# In_Amp.net
KiCad netlist of a schematic drawn in Altium Designer
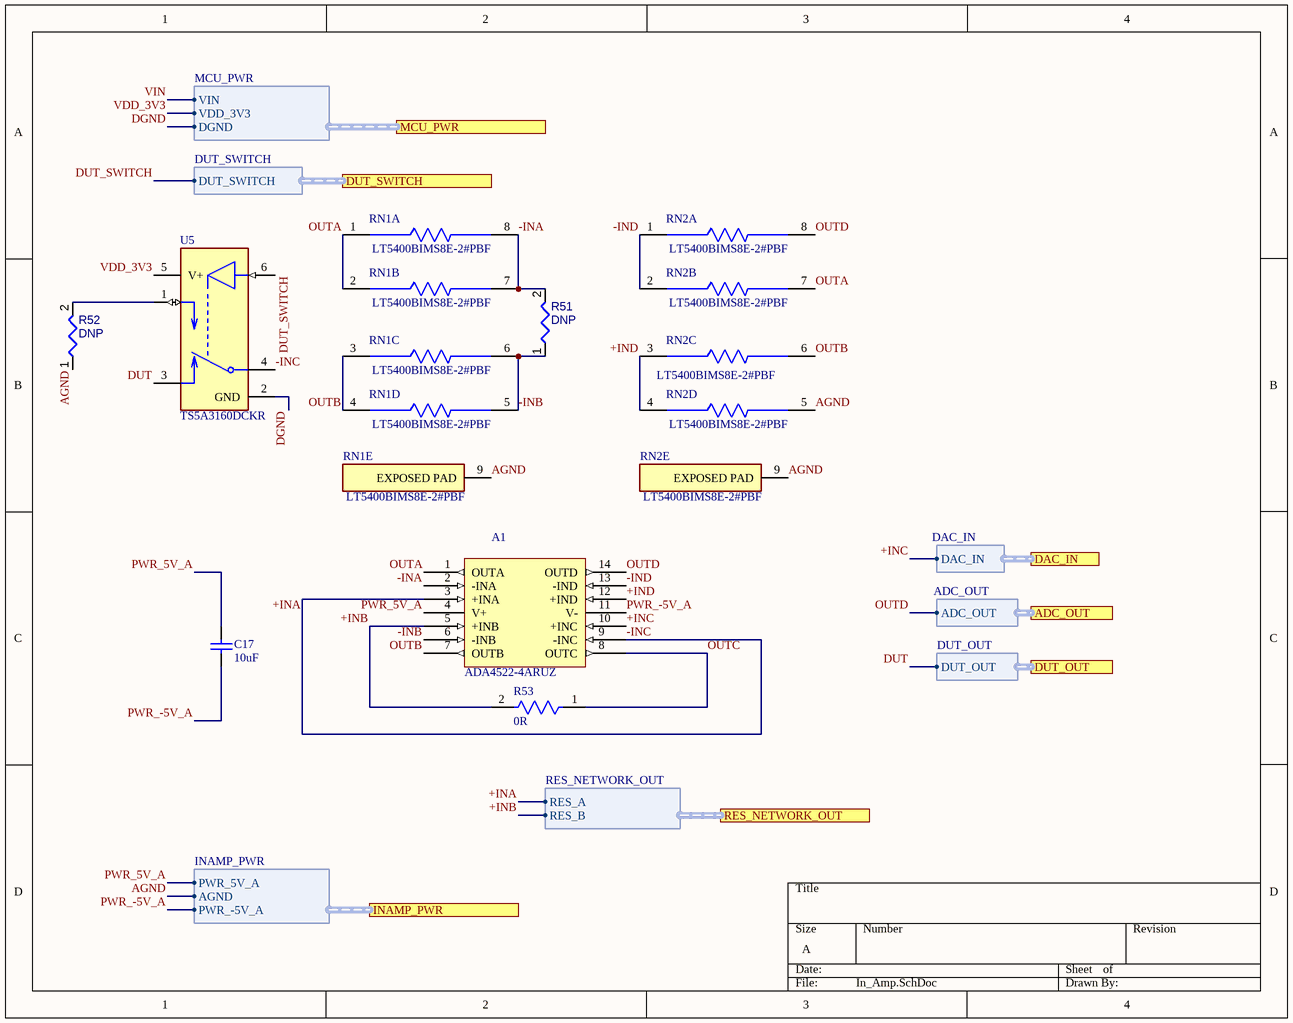
[diagram p0: In_Amp.SchDoc]

(export (version "E")
  (design (tool "Eeschema 10.0.6"))
  (components
    (comp (ref "A1")
      (value "ADA4522-4ARUZ")
      (footprint "TSSOP14")
      (libsource (lib "SchematicLibLovro") (part "AD4522-4ARUZ"))
    )
    (comp (ref "C17")
      (value "10uF")
      (footprint "CAPC2013X135X45ML10T25")
      (fields (field (name "PART NUMBER") "GRM21BR61E106KA73L") (field (name "MANUFACTURER") "Murata"))
      (libsource (lib "Altium Content Vault") (part "CAP"))
    )
    (comp (ref "R51")
      (value "DNP")
      (footprint "RESC1608X55X25ML10T15")
      (description "do not place")
      (libsource (lib "Lovro's workspace") (part "RES-2"))
    )
    (comp (ref "R52")
      (value "DNP")
      (footprint "RESC1608X55X25ML10T15")
      (description "do not place")
      (libsource (lib "Lovro's workspace") (part "RES-2"))
    )
    (comp (ref "R53")
      (value "0R")
      (footprint "FP-CR0603-MFG")
      (description "Thick Film Chip Resistors 0603 0Ω 0.1W 5%")
      (fields (field (name "TOLERANCE") "1%"))
      (libsource (lib "Altium Content Vault") (part "1029c3af85768c4190bb7ad29bc67b5"))
    )
    (comp (ref "RN1")
      (value "LT5400BIMS8E-2#PBF")
      (footprint "FP-MS8E-8-05-08-1662-MFG")
      (description "RES ARRAY 4 RES 1K OHM 8TSSOP")
      (fields
        (field (name "OCTOPART") "https://octopart.com/lt5400ahms8e-4%23pbf-analog+devices-88940367")
        (field (name "MANUFACTURER") "Analog Devices")
      )
      (libsource (lib "Altium Content Vault") (part "2a3fcee17dfe07ed204b7d70d1dfd57"))
    )
    (comp (ref "RN2")
      (value "LT5400BIMS8E-2#PBF")
      (footprint "FP-MS8E-8-05-08-1662-MFG")
      (description "RES ARRAY 4 RES 1K OHM 8TSSOP")
      (fields
        (field (name "OCTOPART") "https://octopart.com/lt5400ahms8e-4%23pbf-analog+devices-88940367")
        (field (name "MANUFACTURER") "Analog Devices")
      )
      (libsource (lib "Altium Content Vault") (part "2a3fcee17dfe07ed204b7d70d1dfd57"))
    )
    (comp (ref "U5")
      (value "TS5A3160DCKR")
      (footprint "FP-DCK0006A-MFG")
      (description "IC SWITCH SPDT SC70-6")
      (fields
        (field (name "OCTOPART") "https://octopart.com/ts5a3160dckr-texas+instruments-665387")
        (field (name "MANUFACTURER") "Texas Instruments")
      )
      (libsource (lib "Altium Content Vault") (part "dd16568d2eba44a85523cc31585f9e4"))
    )
  )
  (nets
    (net (code "7") (name "/+INA") (class "Default")
      (node (ref "A1") (pin "3") (pinfunction "+INA_3") (pintype "input"))
      (node (ref "A1") (pin "9") (pinfunction "-INC_9") (pintype "input"))
      (node (ref "U5") (pin "4") (pinfunction "COM_4") (pintype "passive"))
    )
    (net (code "8") (name "/+INB") (class "Default")
      (node (ref "A1") (pin "5") (pinfunction "+INB_5") (pintype "input"))
      (node (ref "R53") (pin "2") (pinfunction "2_2") (pintype "passive"))
    )
    (net (code "9") (name "/+INC") (class "Default")
      (node (ref "A1") (pin "10") (pinfunction "+INC_10") (pintype "input"))
    )
    (net (code "10") (name "/+IND") (class "Default")
      (node (ref "A1") (pin "12") (pinfunction "+IND_12") (pintype "input"))
      (node (ref "RN2") (pin "3") (pinfunction "1_R3_3") (pintype "passive"))
      (node (ref "RN2") (pin "4") (pinfunction "1_R4_4") (pintype "passive"))
    )
    (net (code "11") (name "/-INA") (class "Default")
      (node (ref "A1") (pin "2") (pinfunction "-INA_2") (pintype "input"))
      (node (ref "R51") (pin "2") (pinfunction "2_2") (pintype "passive"))
      (node (ref "RN1") (pin "7") (pinfunction "2_R2_7") (pintype "passive"))
      (node (ref "RN1") (pin "8") (pinfunction "2_R1_8") (pintype "passive"))
    )
    (net (code "12") (name "/-INB") (class "Default")
      (node (ref "A1") (pin "6") (pinfunction "-INB_6") (pintype "input"))
      (node (ref "R51") (pin "1") (pinfunction "1_1") (pintype "passive"))
      (node (ref "RN1") (pin "5") (pinfunction "2_R4_5") (pintype "passive"))
      (node (ref "RN1") (pin "6") (pinfunction "2_R3_6") (pintype "passive"))
    )
    (net (code "13") (name "/-IND") (class "Default")
      (node (ref "A1") (pin "13") (pinfunction "-IND_13") (pintype "input"))
      (node (ref "RN2") (pin "1") (pinfunction "1_R1_1") (pintype "passive"))
      (node (ref "RN2") (pin "2") (pinfunction "1_R2_2") (pintype "passive"))
    )
    (net (code "14") (name "/AGND") (class "Default")
      (node (ref "R52") (pin "1") (pinfunction "1_1") (pintype "passive"))
      (node (ref "RN1") (pin "9") (pinfunction "EXPOSED_PAD_9") (pintype "passive"))
      (node (ref "RN2") (pin "5") (pinfunction "2_R4_5") (pintype "passive"))
      (node (ref "RN2") (pin "9") (pinfunction "EXPOSED_PAD_9") (pintype "passive"))
    )
    (net (code "15") (name "/DGND") (class "Default")
      (node (ref "U5") (pin "2") (pinfunction "GND_2") (pintype "power_in"))
    )
    (net (code "16") (name "/DUT") (class "Default")
      (node (ref "U5") (pin "3") (pinfunction "NC_3") (pintype "passive"))
    )
    (net (code "17") (name "/DUT_SWITCH") (class "Default")
      (node (ref "U5") (pin "6") (pinfunction "IN_6") (pintype "input"))
    )
    (net (code "18") (name "/OUTA") (class "Default")
      (node (ref "A1") (pin "1") (pinfunction "OUTA_1") (pintype "output"))
      (node (ref "RN1") (pin "1") (pinfunction "1_R1_1") (pintype "passive"))
      (node (ref "RN1") (pin "2") (pinfunction "1_R2_2") (pintype "passive"))
      (node (ref "RN2") (pin "7") (pinfunction "2_R2_7") (pintype "passive"))
    )
    (net (code "19") (name "/OUTB") (class "Default")
      (node (ref "A1") (pin "7") (pinfunction "OUTB_7") (pintype "output"))
      (node (ref "RN1") (pin "3") (pinfunction "1_R3_3") (pintype "passive"))
      (node (ref "RN1") (pin "4") (pinfunction "1_R4_4") (pintype "passive"))
      (node (ref "RN2") (pin "6") (pinfunction "2_R3_6") (pintype "passive"))
    )
    (net (code "20") (name "/OUTC") (class "Default")
      (node (ref "A1") (pin "8") (pinfunction "OUTC_8") (pintype "output"))
      (node (ref "R53") (pin "1") (pinfunction "1_1") (pintype "passive"))
    )
    (net (code "21") (name "/OUTD") (class "Default")
      (node (ref "A1") (pin "14") (pinfunction "OUTD_14") (pintype "output"))
      (node (ref "RN2") (pin "8") (pinfunction "2_R1_8") (pintype "passive"))
    )
    (net (code "22") (name "/PWR_-5V_A") (class "Default")
      (node (ref "A1") (pin "11") (pinfunction "V-_11") (pintype "power_in"))
      (node (ref "C17") (pin "1") (pinfunction "1_1") (pintype "passive"))
    )
    (net (code "23") (name "/PWR_5V_A") (class "Default")
      (node (ref "A1") (pin "4") (pinfunction "V+_4") (pintype "power_in"))
      (node (ref "C17") (pin "2") (pinfunction "2_2") (pintype "passive"))
    )
    (net (code "24") (name "/VDD_3V3") (class "Default")
      (node (ref "U5") (pin "5") (pinfunction "V+_5") (pintype "power_in"))
    )
    (net (code "33") (name "Net-(U5-NO)") (class "Default")
      (node (ref "R52") (pin "2") (pinfunction "2_2") (pintype "passive"))
      (node (ref "U5") (pin "1") (pinfunction "NO_1") (pintype "bidirectional"))
    )
  )
)
